# Master_MicroController_Core.net
KiCad netlist of a schematic drawn in Altium Designer
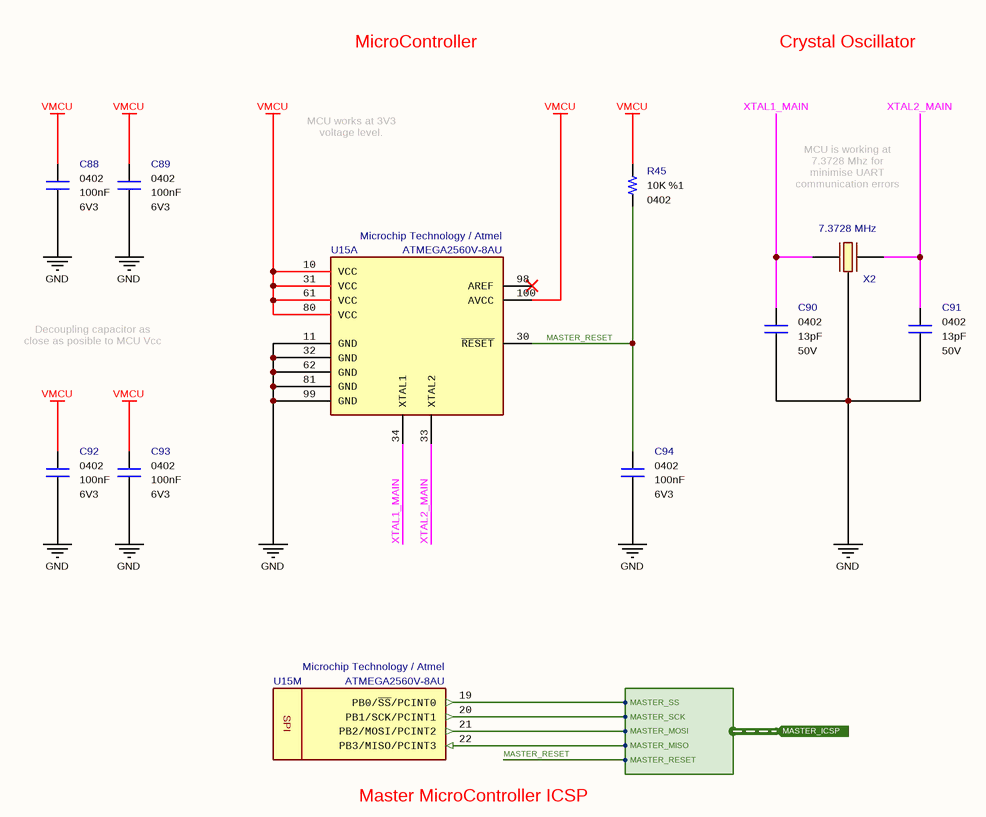
[diagram p0: Master MicroController Core.SchDoc]

(export (version "E")
  (design (tool "Eeschema 10.0.6"))
  (components
    (comp (ref "C88")
      (value "100nF")
      (footprint "CAPACITOR_0402")
      (description "Capacitor - 100nF [0402-6V3] (Ceramic)")
      (fields
        (field (name "TOLERANCE") "%10")
        (field (name "CASE") "0402")
        (field (name "VOLTAGE") "6V3")
        (field (name "MANUFACTURER PART NUMBER") "04026D104KAT4A")
      )
      (libsource (lib "Ovoo_Library") (part "Capacitor - 100nF [0402-6V3]"))
    )
    (comp (ref "C89")
      (value "100nF")
      (footprint "CAPACITOR_0402")
      (description "Capacitor - 100nF [0402-6V3] (Ceramic)")
      (fields
        (field (name "TOLERANCE") "%10")
        (field (name "CASE") "0402")
        (field (name "VOLTAGE") "6V3")
        (field (name "MANUFACTURER PART NUMBER") "04026D104KAT4A")
      )
      (libsource (lib "Ovoo_Library") (part "Capacitor - 100nF [0402-6V3]"))
    )
    (comp (ref "C90")
      (value "13pF")
      (footprint "CAPACITOR_0402")
      (description "Capacitor - 13pF [0402] (Ceramic)")
      (fields
        (field (name "TOLERANCE") "1%")
        (field (name "VOLTAGE") "50V")
        (field (name "CASE") "0402")
        (field (name "MANUFACTURER PART NUMBER") "CBR04C130F5GAC")
      )
      (libsource (lib "Ovoo_Library") (part "Capacitor - 13pF [0402-50V]"))
    )
    (comp (ref "C91")
      (value "13pF")
      (footprint "CAPACITOR_0402")
      (description "Capacitor - 13pF [0402] (Ceramic)")
      (fields
        (field (name "TOLERANCE") "1%")
        (field (name "VOLTAGE") "50V")
        (field (name "CASE") "0402")
        (field (name "MANUFACTURER PART NUMBER") "CBR04C130F5GAC")
      )
      (libsource (lib "Ovoo_Library") (part "Capacitor - 13pF [0402-50V]"))
    )
    (comp (ref "C92")
      (value "100nF")
      (footprint "CAPACITOR_0402")
      (description "Capacitor - 100nF [0402-6V3] (Ceramic)")
      (fields
        (field (name "TOLERANCE") "%10")
        (field (name "CASE") "0402")
        (field (name "VOLTAGE") "6V3")
        (field (name "MANUFACTURER PART NUMBER") "04026D104KAT4A")
      )
      (libsource (lib "Ovoo_Library") (part "Capacitor - 100nF [0402-6V3]"))
    )
    (comp (ref "C93")
      (value "100nF")
      (footprint "CAPACITOR_0402")
      (description "Capacitor - 100nF [0402-6V3] (Ceramic)")
      (fields
        (field (name "TOLERANCE") "%10")
        (field (name "CASE") "0402")
        (field (name "VOLTAGE") "6V3")
        (field (name "MANUFACTURER PART NUMBER") "04026D104KAT4A")
      )
      (libsource (lib "Ovoo_Library") (part "Capacitor - 100nF [0402-6V3]"))
    )
    (comp (ref "C94")
      (value "100nF")
      (footprint "CAPACITOR_0402")
      (description "Capacitor - 100nF [0402-6V3] (Ceramic)")
      (fields
        (field (name "TOLERANCE") "%10")
        (field (name "CASE") "0402")
        (field (name "VOLTAGE") "6V3")
        (field (name "MANUFACTURER PART NUMBER") "04026D104KAT4A")
      )
      (libsource (lib "Ovoo_Library") (part "Capacitor - 100nF [0402-6V3]"))
    )
    (comp (ref "R45")
      (value "10K")
      (footprint "RESISTOR_0402")
      (description "Thick Film Resistors - SMD 1/16 W 10 Kohms 1%")
      (fields
        (field (name "TOLERANCE") "%1")
        (field (name "CASE") "0402")
        (field (name "MANUFACTURER PART NUMBER") "CRCW040210K0FKED")
        (field (name "MOUSER PART NUMBER") "71-CRCW0402-10K-E3")
      )
      (libsource (lib "Ovoo_Library") (part "Resistor - 10K"))
    )
    (comp (ref "U15")
      (value "8-bit MicroController")
      (footprint "TQFP100")
      (description "8-bit Microcontrollers - MCU 256kB Flash 4kB EEPROM 86 I/O Pins")
      (fields
        (field (name "MANUFACTURER PART NUMBER") "ATMEGA2560V-8AU")
        (field (name "MANUFACTURER NAME") "Microchip Technology / Atmel")
      )
      (libsource (lib "Ovoo_Library") (part "IC - ATMEGA2560V-8AU"))
    )
    (comp (ref "X2")
      (value "7.3728 MHz")
      (footprint "ABRACON_CRYSTAL")
      (description "Crystals 7.3728MHz 18pF -40C +85C")
      (fields
        (field (name "MANUFACTURER PART NUMBER") "ABMM2-7.3728MHZ-E2-T")
        (field (name "MOUSER PART NUMBER") "815-ABMM2-7.3-E2-T")
      )
      (libsource (lib "Ovoo_Library") (part "Crystal - 7.3728 MHz (Abracon)"))
    )
  )
  (nets
    (net (code "2") (name "/MASTER_MISO") (class "Default")
      (node (ref "U15") (pin "22") (pinfunction "PB3/MISO/PCINT3_22") (pintype "passive"))
    )
    (net (code "3") (name "/MASTER_MOSI") (class "Default")
      (node (ref "U15") (pin "21") (pinfunction "PB2/MOSI/PCINT2_21") (pintype "passive"))
    )
    (net (code "4") (name "/MASTER_RESET") (class "Default")
      (node (ref "C94") (pin "2") (pinfunction "2_2") (pintype "passive"))
      (node (ref "R45") (pin "1") (pinfunction "1_1") (pintype "passive"))
      (node (ref "U15") (pin "30") (pinfunction "~{RESET}_30") (pintype "passive"))
    )
    (net (code "5") (name "/MASTER_SCK") (class "Default")
      (node (ref "U15") (pin "20") (pinfunction "PB1/SCK/PCINT1_20") (pintype "passive"))
    )
    (net (code "6") (name "/MASTER_SS") (class "Default")
      (node (ref "U15") (pin "19") (pinfunction "PB0/~{SS}/PCINT0_19") (pintype "passive"))
    )
    (net (code "7") (name "/XTAL1_MAIN") (class "Default")
      (node (ref "C90") (pin "2") (pinfunction "2_2") (pintype "passive"))
      (node (ref "U15") (pin "34") (pinfunction "XTAL1_34") (pintype "passive"))
      (node (ref "X2") (pin "3") (pinfunction "OUT/IN_3") (pintype "passive"))
    )
    (net (code "8") (name "/XTAL2_MAIN") (class "Default")
      (node (ref "C91") (pin "2") (pinfunction "2_2") (pintype "passive"))
      (node (ref "U15") (pin "33") (pinfunction "XTAL2_33") (pintype "passive"))
      (node (ref "X2") (pin "1") (pinfunction "IN/OUT_1") (pintype "passive"))
    )
    (net (code "10") (name "GND") (class "Default")
      (node (ref "C88") (pin "1") (pinfunction "1_1") (pintype "passive"))
      (node (ref "C89") (pin "1") (pinfunction "1_1") (pintype "passive"))
      (node (ref "C90") (pin "1") (pinfunction "1_1") (pintype "passive"))
      (node (ref "C91") (pin "1") (pinfunction "1_1") (pintype "passive"))
      (node (ref "C92") (pin "1") (pinfunction "1_1") (pintype "passive"))
      (node (ref "C93") (pin "1") (pinfunction "1_1") (pintype "passive"))
      (node (ref "C94") (pin "1") (pinfunction "1_1") (pintype "passive"))
      (node (ref "U15") (pin "11") (pinfunction "GND_11") (pintype "passive"))
      (node (ref "U15") (pin "32") (pinfunction "GND_32") (pintype "passive"))
      (node (ref "U15") (pin "62") (pinfunction "GND_62") (pintype "passive"))
      (node (ref "U15") (pin "81") (pinfunction "GND_81") (pintype "passive"))
      (node (ref "U15") (pin "99") (pinfunction "GND_99") (pintype "passive"))
      (node (ref "X2") (pin "2") (pinfunction "GND_2") (pintype "passive"))
    )
    (net (code "11") (name "VMCU") (class "Default")
      (node (ref "C88") (pin "2") (pinfunction "2_2") (pintype "passive"))
      (node (ref "C89") (pin "2") (pinfunction "2_2") (pintype "passive"))
      (node (ref "C92") (pin "2") (pinfunction "2_2") (pintype "passive"))
      (node (ref "C93") (pin "2") (pinfunction "2_2") (pintype "passive"))
      (node (ref "R45") (pin "2") (pinfunction "2_2") (pintype "passive"))
      (node (ref "U15") (pin "10") (pinfunction "VCC_10") (pintype "power_in"))
      (node (ref "U15") (pin "100") (pinfunction "AVCC_100") (pintype "passive"))
      (node (ref "U15") (pin "31") (pinfunction "VCC_31") (pintype "power_in"))
      (node (ref "U15") (pin "61") (pinfunction "VCC_61") (pintype "power_in"))
      (node (ref "U15") (pin "80") (pinfunction "VCC_80") (pintype "power_in"))
    )
    (net (code "12") (name "unconnected-(U15A-AREF-Pad98)") (class "Default")
      (node (ref "U15") (pin "98") (pinfunction "AREF_98") (pintype "passive+no_connect"))
    )
    (net (code "13") (name "unconnected-(X2-GND-Pad4)") (class "Default")
      (node (ref "X2") (pin "4") (pinfunction "GND_4") (pintype "passive"))
    )
  )
)
